# Schematic_page2.net
KiCad netlist of a schematic drawn in Altium Designer
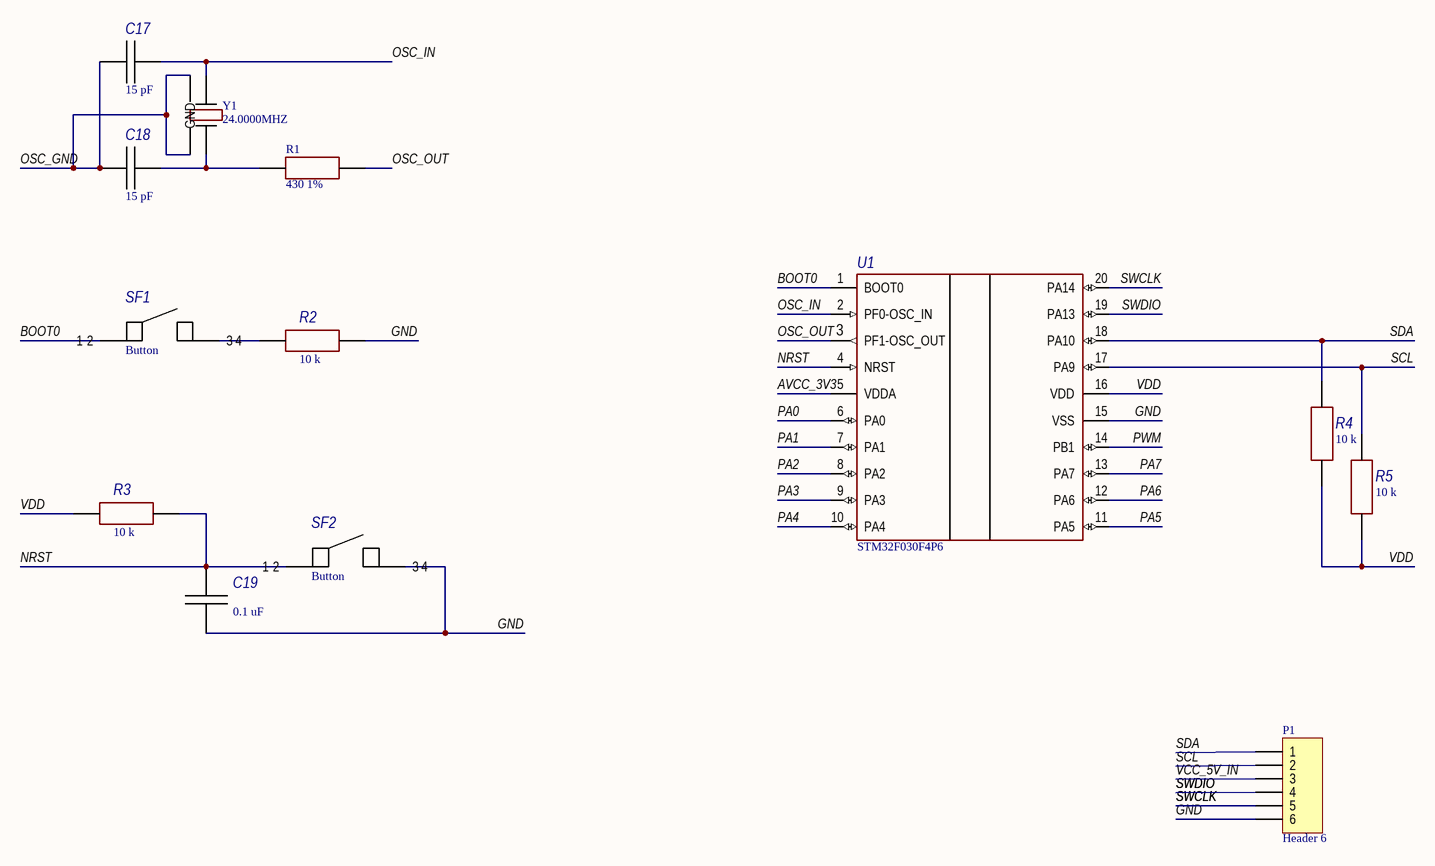
[diagram p0: Schematic_page2.SchDoc]

(export (version "E")
  (design (tool "Eeschema 10.0.6"))
  (components
    (comp (ref "C17")
      (value "15 pF")
      (footprint "C0603")
      (fields (field (name "MANUFACTURER") "Murata Manufacturing"))
      (libsource (lib "") (part "Capasitor_1"))
    )
    (comp (ref "C18")
      (value "15 pF")
      (footprint "C0603")
      (fields (field (name "MANUFACTURER") "Murata Manufacturing"))
      (libsource (lib "") (part "Capasitor_1"))
    )
    (comp (ref "C19")
      (value "0.1 uF")
      (footprint "C0603")
      (fields (field (name "MANUFACTURER") "Murata Manufacturing"))
      (libsource (lib "Linalance_lib") (part "Capasitor"))
    )
    (comp (ref "P1")
      (value "Header 6")
      (footprint "HDR1X6")
      (description "Header, 6-Pin")
      (fields (field (name "PUBLISHER") "Altium Limited"))
      (libsource (lib "Miscellaneous Connectors") (part "Header 6"))
    )
    (comp (ref "R1")
      (value "430 1%")
      (footprint "R0603")
      (description "Rext.")
      (libsource (lib "Linalance_lib") (part "Resistor"))
    )
    (comp (ref "R2")
      (value "10 k")
      (footprint "R0603")
      (fields (field (name "MANUFACTURER") "YAGEO"))
      (libsource (lib "") (part "Resistor_2"))
    )
    (comp (ref "R3")
      (value "10 k")
      (footprint "R0603")
      (fields (field (name "MANUFACTURER") "YAGEO"))
      (libsource (lib "Linalance_lib") (part "Resistor"))
    )
    (comp (ref "R4")
      (value "10 k")
      (footprint "R0603")
      (fields (field (name "MANUFACTURER") "YAGEO"))
      (libsource (lib "") (part "Resistor_1"))
    )
    (comp (ref "R5")
      (value "10 k")
      (footprint "R0603")
      (fields (field (name "MANUFACTURER") "YAGEO"))
      (libsource (lib "") (part "Resistor_1"))
    )
    (comp (ref "SF1")
      (value "Button")
      (footprint "KMR221GLFS")
      (description "SWITCH TACTILE SPST-NO 0.05A 32V")
      (fields (field (name "MANUFACTURER") "C&K"))
      (libsource (lib "Linalance_lib") (part "Button"))
    )
    (comp (ref "SF2")
      (value "Button")
      (footprint "KMR221GLFS")
      (description "SWITCH TACTILE SPST-NO 0.05A 32V")
      (fields (field (name "MANUFACTURER") "C&K"))
      (libsource (lib "Linalance_lib") (part "Button"))
    )
    (comp (ref "U1")
      (value "STM32F030F4P6")
      (footprint "TSSOP-20")
      (description "IC MCU 32BIT 16KB FLASH 20TSSOP")
      (fields (field (name "MANUFACTURER") "STMicroelectronics"))
      (libsource (lib "Linalance_lib") (part "STM32F030F4P6"))
    )
    (comp (ref "Y1")
      (value "24.0000MHZ")
      (footprint "TSX-3225")
      (description "CRYSTAL 24.0000MHZ 9PF SMD")
      (fields (field (name "MANUFACTURER") "EPSON"))
      (libsource (lib "Linalance_lib") (part "Crystal"))
    )
  )
  (nets
    (net (code "1") (name "/AVCC_3V3") (class "Default")
      (node (ref "U1") (pin "5") (pinfunction "VDDA_5") (pintype "power_in"))
    )
    (net (code "2") (name "/BOOT0") (class "Default")
      (node (ref "SF1") (pin "1") (pinfunction "1_1") (pintype "passive"))
      (node (ref "SF1") (pin "2") (pinfunction "2_2") (pintype "passive"))
      (node (ref "U1") (pin "1") (pinfunction "BOOT0_1") (pintype "passive"))
    )
    (net (code "3") (name "/GND") (class "Default")
      (node (ref "C19") (pin "2") (pintype "passive"))
      (node (ref "P1") (pin "6") (pinfunction "6_6") (pintype "passive"))
      (node (ref "R2") (pin "1") (pintype "passive"))
      (node (ref "SF2") (pin "4") (pinfunction "4_4") (pintype "passive"))
      (node (ref "U1") (pin "15") (pinfunction "VSS_15") (pintype "power_in"))
    )
    (net (code "4") (name "/NRST") (class "Default")
      (node (ref "C19") (pin "1") (pintype "passive"))
      (node (ref "R3") (pin "2") (pintype "passive"))
      (node (ref "SF2") (pin "1") (pinfunction "1_1") (pintype "passive"))
      (node (ref "SF2") (pin "2") (pinfunction "2_2") (pintype "passive"))
      (node (ref "U1") (pin "4") (pinfunction "NRST_4") (pintype "input"))
    )
    (net (code "5") (name "/OSC_GND") (class "Default")
      (node (ref "C17") (pin "2") (pintype "passive"))
      (node (ref "C18") (pin "2") (pintype "passive"))
      (node (ref "Y1") (pin "2") (pinfunction "GND_2") (pintype "passive"))
      (node (ref "Y1") (pin "4") (pinfunction "GND_4") (pintype "passive"))
    )
    (net (code "6") (name "/OSC_IN") (class "Default")
      (node (ref "C17") (pin "1") (pintype "passive"))
      (node (ref "U1") (pin "2") (pinfunction "PF0-OSC_IN_2") (pintype "input"))
      (node (ref "Y1") (pin "1") (pintype "passive"))
    )
    (net (code "7") (name "/OSC_OUT") (class "Default")
      (node (ref "R1") (pin "2") (pintype "passive"))
      (node (ref "U1") (pin "3") (pinfunction "PF1-OSC_OUT_3") (pintype "output"))
    )
    (net (code "8") (name "/PA0") (class "Default")
      (node (ref "U1") (pin "6") (pinfunction "PA0_6") (pintype "bidirectional"))
    )
    (net (code "9") (name "/PA1") (class "Default")
      (node (ref "U1") (pin "7") (pinfunction "PA1_7") (pintype "bidirectional"))
    )
    (net (code "10") (name "/PA2") (class "Default")
      (node (ref "U1") (pin "8") (pinfunction "PA2_8") (pintype "bidirectional"))
    )
    (net (code "11") (name "/PA3") (class "Default")
      (node (ref "U1") (pin "9") (pinfunction "PA3_9") (pintype "bidirectional"))
    )
    (net (code "12") (name "/PA4") (class "Default")
      (node (ref "U1") (pin "10") (pinfunction "PA4_10") (pintype "bidirectional"))
    )
    (net (code "13") (name "/PA5") (class "Default")
      (node (ref "U1") (pin "11") (pinfunction "PA5_11") (pintype "bidirectional"))
    )
    (net (code "14") (name "/PA6") (class "Default")
      (node (ref "U1") (pin "12") (pinfunction "PA6_12") (pintype "bidirectional"))
    )
    (net (code "15") (name "/PA7") (class "Default")
      (node (ref "U1") (pin "13") (pinfunction "PA7_13") (pintype "bidirectional"))
    )
    (net (code "16") (name "/PWM") (class "Default")
      (node (ref "U1") (pin "14") (pinfunction "PB1_14") (pintype "bidirectional"))
    )
    (net (code "17") (name "/SCL") (class "Default")
      (node (ref "P1") (pin "2") (pinfunction "2_2") (pintype "passive"))
      (node (ref "R5") (pin "2") (pintype "passive"))
      (node (ref "U1") (pin "17") (pinfunction "PA9_17") (pintype "bidirectional"))
    )
    (net (code "18") (name "/SDA") (class "Default")
      (node (ref "P1") (pin "1") (pinfunction "1_1") (pintype "passive"))
      (node (ref "R4") (pin "2") (pintype "passive"))
      (node (ref "U1") (pin "18") (pinfunction "PA10_18") (pintype "bidirectional"))
    )
    (net (code "19") (name "/SWCLK") (class "Default")
      (node (ref "P1") (pin "5") (pinfunction "5_5") (pintype "passive"))
      (node (ref "U1") (pin "20") (pinfunction "PA14_20") (pintype "bidirectional"))
    )
    (net (code "20") (name "/SWDIO") (class "Default")
      (node (ref "P1") (pin "4") (pinfunction "4_4") (pintype "passive"))
      (node (ref "U1") (pin "19") (pinfunction "PA13_19") (pintype "bidirectional"))
    )
    (net (code "21") (name "/VCC_5V_IN") (class "Default")
      (node (ref "P1") (pin "3") (pinfunction "3_3") (pintype "passive"))
    )
    (net (code "22") (name "/VDD") (class "Default")
      (node (ref "R3") (pin "1") (pintype "passive"))
      (node (ref "R4") (pin "1") (pintype "passive"))
      (node (ref "R5") (pin "1") (pintype "passive"))
      (node (ref "U1") (pin "16") (pinfunction "VDD_16") (pintype "power_in"))
    )
    (net (code "23") (name "Net-(C18-Pad1)") (class "Default")
      (node (ref "C18") (pin "1") (pintype "passive"))
      (node (ref "R1") (pin "1") (pintype "passive"))
      (node (ref "Y1") (pin "3") (pintype "passive"))
    )
    (net (code "24") (name "Net-(R2-Pad2)") (class "Default")
      (node (ref "R2") (pin "2") (pintype "passive"))
      (node (ref "SF1") (pin "4") (pinfunction "4_4") (pintype "passive"))
    )
    (net (code "25") (name "unconnected-(SF1-Pad3)") (class "Default")
      (node (ref "SF1") (pin "3") (pinfunction "3_3") (pintype "passive"))
    )
    (net (code "26") (name "unconnected-(SF2-Pad3)") (class "Default")
      (node (ref "SF2") (pin "3") (pinfunction "3_3") (pintype "passive"))
    )
  )
)
